# Robot-Power_V4_0.net
KiCad netlist of a schematic drawn in Altium Designer
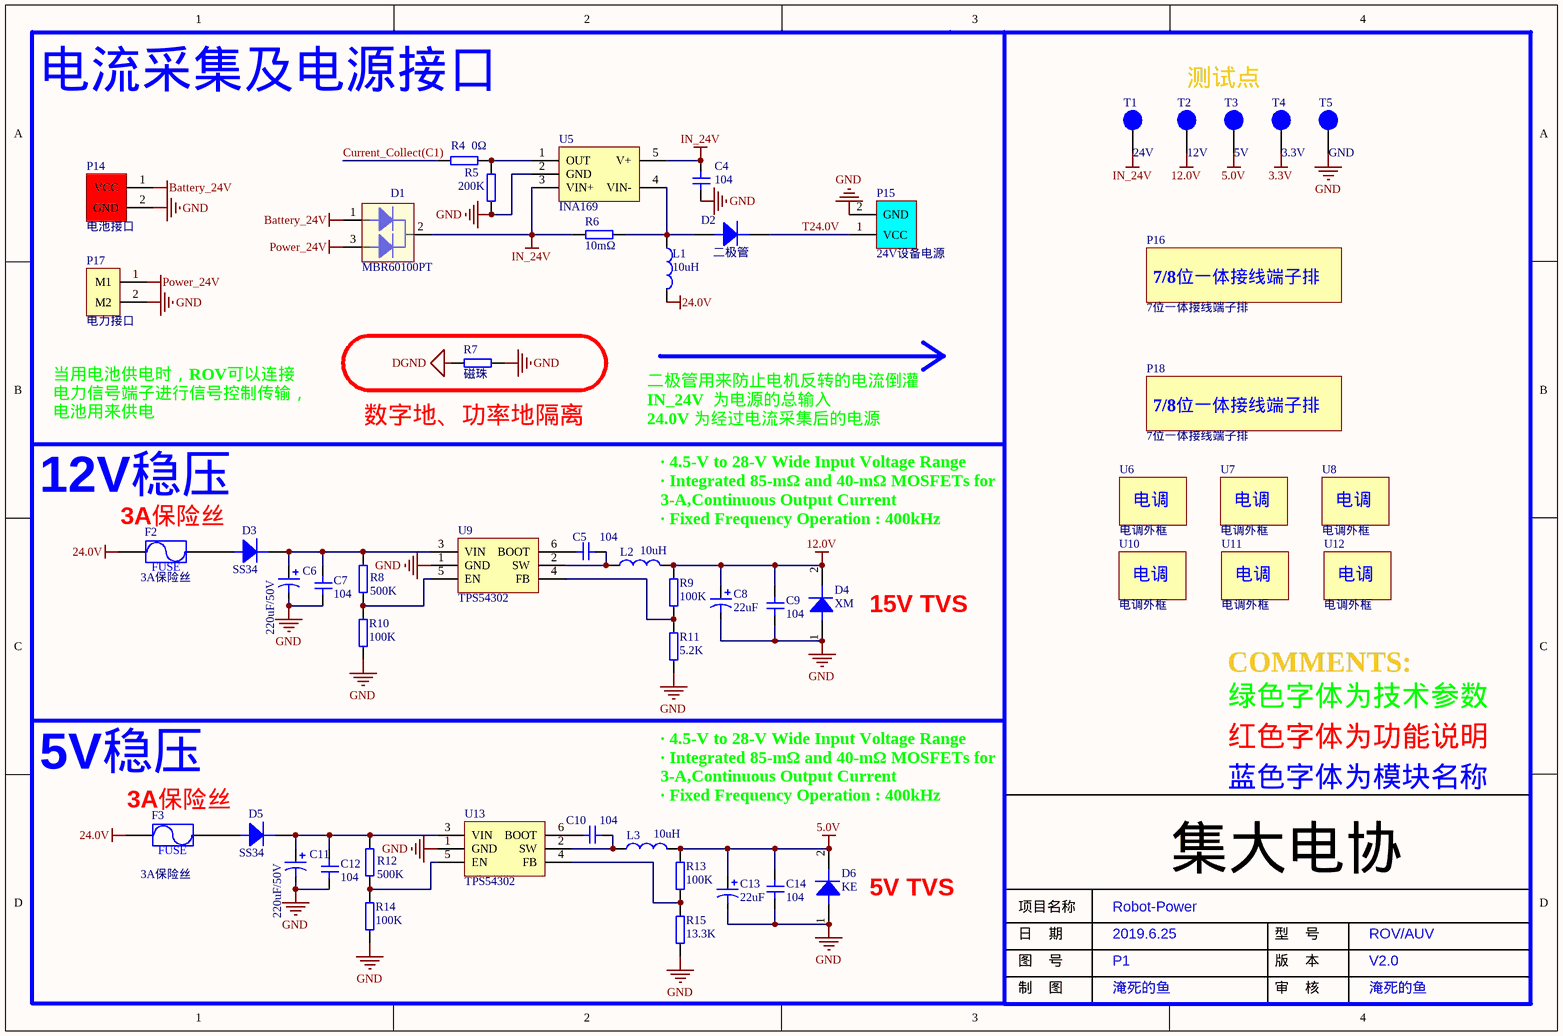
[diagram p0: Robot-Power V4.0.SchDoc]

(export (version "E")
  (design (tool "Eeschema 10.0.6"))
  (components
    (comp (ref "C4")
      (value "104")
      (footprint "0805C")
      (description "无极贴片电容")
      (libsource (lib "集大电协1.5") (part "Cap1"))
    )
    (comp (ref "C5")
      (value "104")
      (footprint "0805C")
      (description "无极贴片电容")
      (libsource (lib "集大电协1.5") (part "Cap1"))
    )
    (comp (ref "C6")
      (value "220uF/50V")
      (footprint "RB.1.2")
      (description "直插极性电容")
      (libsource (lib "集大电协1.5") (part "Cap3"))
    )
    (comp (ref "C7")
      (value "104")
      (footprint "0805C")
      (description "无极贴片电容")
      (libsource (lib "集大电协1.5") (part "Cap1"))
    )
    (comp (ref "C8")
      (value "22uF")
      (footprint "TAJ-C")
      (description "极性贴片电容")
      (libsource (lib "集大电协1.5") (part "Pol Cap"))
    )
    (comp (ref "C9")
      (value "104")
      (footprint "0805C")
      (description "无极贴片电容")
      (libsource (lib "集大电协1.5") (part "Cap1"))
    )
    (comp (ref "C10")
      (value "104")
      (footprint "0805C")
      (description "无极贴片电容")
      (libsource (lib "集大电协1.5") (part "Cap1"))
    )
    (comp (ref "C11")
      (value "220uF/50V")
      (footprint "RB.1.2")
      (description "直插极性电容")
      (libsource (lib "集大电协1.5") (part "Cap3"))
    )
    (comp (ref "C12")
      (value "104")
      (footprint "0805C")
      (description "无极贴片电容")
      (libsource (lib "集大电协1.5") (part "Cap1"))
    )
    (comp (ref "C13")
      (value "22uF")
      (footprint "TAJ-C")
      (description "极性贴片电容")
      (libsource (lib "集大电协1.5") (part "Pol Cap"))
    )
    (comp (ref "C14")
      (value "104")
      (footprint "0805C")
      (description "无极贴片电容")
      (libsource (lib "集大电协1.5") (part "Cap1"))
    )
    (comp (ref "D1")
      (value "MBR60100PT")
      (footprint "TO-247LS")
      (libsource (lib "集大电协1.5") (part "MBR60100PT"))
    )
    (comp (ref "D2") (value "二极管") (footprint "二极管(大功率)") (libsource (lib "集大电协2.0") (part "Diode")))
    (comp (ref "D3")
      (value "SS34")
      (footprint "SMA/DO-214AC")
      (description "二极管")
      (libsource (lib "") (part "Diode_1"))
    )
    (comp (ref "D4")
      (value "XM")
      (footprint "SMBJ")
      (description "二极管")
      (libsource (lib "集大电协1.5") (part "Diode"))
    )
    (comp (ref "D5")
      (value "SS34")
      (footprint "SMA/DO-214AC")
      (description "二极管")
      (libsource (lib "") (part "Diode_1"))
    )
    (comp (ref "D6")
      (value "KE")
      (footprint "SMBJ")
      (description "二极管")
      (libsource (lib "集大电协1.5") (part "Diode"))
    )
    (comp (ref "F2")
      (value "3A保险丝")
      (footprint "FUSE-1206")
      (description "保险丝")
      (libsource (lib "集大电协1.2") (part "Fuse"))
    )
    (comp (ref "F3")
      (value "3A保险丝")
      (footprint "FUSE-1206")
      (description "保险丝")
      (libsource (lib "集大电协1.2") (part "Fuse"))
    )
    (comp (ref "L1")
      (value "10uH")
      (footprint "CDRH124")
      (description "电感")
      (libsource (lib "集大电协1.5") (part "L"))
    )
    (comp (ref "L2")
      (value "10uH")
      (footprint "CDRH124")
      (description "电感")
      (libsource (lib "") (part "L_1"))
    )
    (comp (ref "L3")
      (value "10uH")
      (footprint "CDRH124")
      (description "电感")
      (libsource (lib "") (part "L_1"))
    )
    (comp (ref "P14") (value "电池接口") (footprint "XT60-F") (libsource (lib "集大电协1.5") (part "电源端子")))
    (comp (ref "P15") (value "24V设备电源") (footprint "XT60-F") (libsource (lib "集大电协1.5") (part "推进器电源")))
    (comp (ref "P16")
      (value "7位一体接线端子排")
      (footprint "7/8一体接线端子")
      (libsource (lib "集大电协1.5") (part "7位一体接线端子排"))
    )
    (comp (ref "P17")
      (value "电力接口")
      (footprint "XT60-F")
      (description "2PIN")
      (libsource (lib "集大电协1.5") (part "接线端子-2PIN"))
    )
    (comp (ref "P18")
      (value "7位一体接线端子排")
      (footprint "7/8一体接线端子")
      (libsource (lib "集大电协1.5") (part "7位一体接线端子排"))
    )
    (comp (ref "R4")
      (value "0Ω")
      (footprint "0805R")
      (description "电阻")
      (libsource (lib "集大电协1.5") (part "Res"))
    )
    (comp (ref "R5")
      (value "200K")
      (footprint "0805R")
      (description "电阻")
      (libsource (lib "集大电协1.5") (part "Res"))
    )
    (comp (ref "R6")
      (value "10mΩ")
      (footprint "2512R")
      (description "电阻")
      (libsource (lib "集大电协1.5") (part "Res"))
    )
    (comp (ref "R7")
      (value "磁珠")
      (footprint "1210R")
      (description "电阻")
      (libsource (lib "集大电协1.2") (part "Res"))
    )
    (comp (ref "R8")
      (value "500K")
      (footprint "0805R")
      (description "电阻")
      (libsource (lib "集大电协1.5") (part "Res"))
    )
    (comp (ref "R9")
      (value "100K")
      (footprint "0805R")
      (description "电阻")
      (libsource (lib "集大电协1.5") (part "Res"))
    )
    (comp (ref "R10")
      (value "100K")
      (footprint "0805R")
      (description "电阻")
      (libsource (lib "集大电协1.5") (part "Res"))
    )
    (comp (ref "R11")
      (value "5.2K")
      (footprint "0805R")
      (description "电阻")
      (libsource (lib "集大电协1.5") (part "Res"))
    )
    (comp (ref "R12")
      (value "500K")
      (footprint "0805R")
      (description "电阻")
      (libsource (lib "集大电协1.5") (part "Res"))
    )
    (comp (ref "R13")
      (value "100K")
      (footprint "0805R")
      (description "电阻")
      (libsource (lib "集大电协1.5") (part "Res"))
    )
    (comp (ref "R14")
      (value "100K")
      (footprint "0805R")
      (description "电阻")
      (libsource (lib "集大电协1.5") (part "Res"))
    )
    (comp (ref "R15")
      (value "13.3K")
      (footprint "0805R")
      (description "电阻")
      (libsource (lib "集大电协1.5") (part "Res"))
    )
    (comp (ref "T1")
      (value "24V")
      (footprint "HEADER 1")
      (description "测试点")
      (libsource (lib "集大电协1.2") (part "测试点"))
    )
    (comp (ref "T2")
      (value "12V")
      (footprint "HEADER 1")
      (description "测试点")
      (libsource (lib "集大电协1.2") (part "测试点"))
    )
    (comp (ref "T3")
      (value "5V")
      (footprint "HEADER 1")
      (description "测试点")
      (libsource (lib "集大电协1.2") (part "测试点"))
    )
    (comp (ref "T4")
      (value "3.3V")
      (footprint "HEADER 1")
      (description "测试点")
      (libsource (lib "集大电协1.2") (part "测试点"))
    )
    (comp (ref "T5")
      (value "GND")
      (footprint "HEADER 1")
      (description "测试点")
      (libsource (lib "集大电协1.2") (part "测试点"))
    )
    (comp (ref "U5") (value "INA169") (footprint "SOT23-5") (libsource (lib "集大电协1.5") (part "INA169")))
    (comp (ref "U6") (value "电调外框") (footprint "电调外框") (libsource (lib "集大电协1.5") (part "电调")))
    (comp (ref "U7") (value "电调外框") (footprint "电调外框") (libsource (lib "集大电协1.5") (part "电调")))
    (comp (ref "U8") (value "电调外框") (footprint "电调外框") (libsource (lib "集大电协1.5") (part "电调")))
    (comp (ref "U9") (value "TPS54302") (footprint "SOT23-6") (libsource (lib "集大电协1.5") (part "TPS54302")))
    (comp (ref "U10") (value "电调外框") (footprint "电调外框") (libsource (lib "集大电协1.5") (part "电调")))
    (comp (ref "U11") (value "电调外框") (footprint "电调外框") (libsource (lib "集大电协1.5") (part "电调")))
    (comp (ref "U12") (value "电调外框") (footprint "电调外框") (libsource (lib "集大电协1.5") (part "电调")))
    (comp (ref "U13") (value "TPS54302") (footprint "SOT23-6") (libsource (lib "集大电协1.5") (part "TPS54302")))
  )
  (nets
    (net (code "1") (name "/Current_Collect(C1)") (class "Default")
      (node (ref "R4") (pin "1") (pinfunction "1_1") (pintype "passive"))
    )
    (net (code "2") (name "/T24.0V") (class "Default")
      (node (ref "D2") (pin "2") (pinfunction "2_2") (pintype "passive"))
      (node (ref "P15") (pin "1") (pinfunction "VCC_1") (pintype "passive"))
    )
    (net (code "3") (name "3.3V") (class "Default")
      (node (ref "T4") (pin "1") (pinfunction "1_1") (pintype "passive"))
    )
    (net (code "4") (name "5.0V") (class "Default")
      (node (ref "C13") (pin "1") (pinfunction "1_1") (pintype "passive"))
      (node (ref "C14") (pin "2") (pinfunction "2_2") (pintype "passive"))
      (node (ref "D6") (pin "2") (pinfunction "2_2") (pintype "passive"))
      (node (ref "L3") (pin "2") (pinfunction "2_2") (pintype "passive"))
      (node (ref "R13") (pin "2") (pinfunction "2_2") (pintype "passive"))
      (node (ref "T3") (pin "1") (pinfunction "1_1") (pintype "passive"))
    )
    (net (code "5") (name "12.0V") (class "Default")
      (node (ref "C8") (pin "1") (pinfunction "1_1") (pintype "passive"))
      (node (ref "C9") (pin "2") (pinfunction "2_2") (pintype "passive"))
      (node (ref "D4") (pin "2") (pinfunction "2_2") (pintype "passive"))
      (node (ref "L2") (pin "2") (pinfunction "2_2") (pintype "passive"))
      (node (ref "R9") (pin "2") (pinfunction "2_2") (pintype "passive"))
      (node (ref "T2") (pin "1") (pinfunction "1_1") (pintype "passive"))
    )
    (net (code "6") (name "24.0V") (class "Default")
      (node (ref "F2") (pin "1") (pinfunction "1_1") (pintype "passive"))
      (node (ref "F3") (pin "1") (pinfunction "1_1") (pintype "passive"))
      (node (ref "L1") (pin "2") (pinfunction "2_2") (pintype "passive"))
    )
    (net (code "7") (name "Battery_24V") (class "Default")
      (node (ref "D1") (pin "1") (pintype "passive"))
      (node (ref "P14") (pin "1") (pinfunction "VCC_1") (pintype "passive"))
    )
    (net (code "8") (name "DGND") (class "Default")
      (node (ref "R7") (pin "2") (pinfunction "2_2") (pintype "passive"))
    )
    (net (code "9") (name "GND") (class "Default")
      (node (ref "C11") (pin "2") (pinfunction "2_2") (pintype "passive"))
      (node (ref "C12") (pin "1") (pinfunction "1_1") (pintype "passive"))
      (node (ref "C13") (pin "2") (pinfunction "2_2") (pintype "passive"))
      (node (ref "C14") (pin "1") (pinfunction "1_1") (pintype "passive"))
      (node (ref "C4") (pin "1") (pinfunction "1_1") (pintype "passive"))
      (node (ref "C6") (pin "2") (pinfunction "2_2") (pintype "passive"))
      (node (ref "C7") (pin "1") (pinfunction "1_1") (pintype "passive"))
      (node (ref "C8") (pin "2") (pinfunction "2_2") (pintype "passive"))
      (node (ref "C9") (pin "1") (pinfunction "1_1") (pintype "passive"))
      (node (ref "D4") (pin "1") (pintype "passive"))
      (node (ref "D6") (pin "1") (pintype "passive"))
      (node (ref "P14") (pin "2") (pinfunction "GND_2") (pintype "passive"))
      (node (ref "P15") (pin "2") (pinfunction "GND_2") (pintype "passive"))
      (node (ref "P17") (pin "2") (pinfunction "M2_2") (pintype "passive"))
      (node (ref "R10") (pin "1") (pinfunction "1_1") (pintype "passive"))
      (node (ref "R11") (pin "1") (pinfunction "1_1") (pintype "passive"))
      (node (ref "R14") (pin "1") (pinfunction "1_1") (pintype "passive"))
      (node (ref "R15") (pin "1") (pinfunction "1_1") (pintype "passive"))
      (node (ref "R5") (pin "2") (pinfunction "2_2") (pintype "passive"))
      (node (ref "R7") (pin "1") (pinfunction "1_1") (pintype "passive"))
      (node (ref "T5") (pin "1") (pinfunction "1_1") (pintype "passive"))
      (node (ref "U13") (pin "1") (pinfunction "GND_1") (pintype "passive"))
      (node (ref "U5") (pin "2") (pinfunction "GND_2") (pintype "passive"))
      (node (ref "U9") (pin "1") (pinfunction "GND_1") (pintype "passive"))
    )
    (net (code "10") (name "IN_24V") (class "Default")
      (node (ref "C4") (pin "2") (pinfunction "2_2") (pintype "passive"))
      (node (ref "D1") (pin "2") (pinfunction "2_2") (pintype "passive"))
      (node (ref "R6") (pin "2") (pinfunction "2_2") (pintype "passive"))
      (node (ref "T1") (pin "1") (pinfunction "1_1") (pintype "passive"))
      (node (ref "U5") (pin "3") (pinfunction "VIN+_3") (pintype "passive"))
      (node (ref "U5") (pin "5") (pinfunction "V+_5") (pintype "passive"))
    )
    (net (code "11") (name "Net-(D3-Pad1)") (class "Default")
      (node (ref "D3") (pin "1") (pintype "passive"))
      (node (ref "F2") (pin "2") (pinfunction "2_2") (pintype "passive"))
    )
    (net (code "12") (name "Net-(D5-Pad1)") (class "Default")
      (node (ref "D5") (pin "1") (pintype "passive"))
      (node (ref "F3") (pin "2") (pinfunction "2_2") (pintype "passive"))
    )
    (net (code "13") (name "Net-(U5-OUT)") (class "Default")
      (node (ref "R4") (pin "2") (pinfunction "2_2") (pintype "passive"))
      (node (ref "R5") (pin "1") (pinfunction "1_1") (pintype "passive"))
      (node (ref "U5") (pin "1") (pinfunction "OUT_1") (pintype "passive"))
    )
    (net (code "14") (name "Net-(U5-VIN-)") (class "Default")
      (node (ref "D2") (pin "1") (pinfunction "1_1") (pintype "passive"))
      (node (ref "L1") (pin "1") (pinfunction "1_1") (pintype "passive"))
      (node (ref "R6") (pin "1") (pinfunction "1_1") (pintype "passive"))
      (node (ref "U5") (pin "4") (pinfunction "VIN-_4") (pintype "passive"))
    )
    (net (code "15") (name "Net-(U9-BOOT)") (class "Default")
      (node (ref "C5") (pin "2") (pinfunction "2_2") (pintype "passive"))
      (node (ref "U9") (pin "6") (pinfunction "BOOT_6") (pintype "passive"))
    )
    (net (code "16") (name "Net-(U9-EN)") (class "Default")
      (node (ref "R10") (pin "2") (pinfunction "2_2") (pintype "passive"))
      (node (ref "R8") (pin "1") (pinfunction "1_1") (pintype "passive"))
      (node (ref "U9") (pin "5") (pinfunction "EN_5") (pintype "passive"))
    )
    (net (code "17") (name "Net-(U9-FB)") (class "Default")
      (node (ref "R11") (pin "2") (pinfunction "2_2") (pintype "passive"))
      (node (ref "R9") (pin "1") (pinfunction "1_1") (pintype "passive"))
      (node (ref "U9") (pin "4") (pinfunction "FB_4") (pintype "passive"))
    )
    (net (code "18") (name "Net-(U9-SW)") (class "Default")
      (node (ref "C5") (pin "1") (pinfunction "1_1") (pintype "passive"))
      (node (ref "L2") (pin "1") (pinfunction "1_1") (pintype "passive"))
      (node (ref "U9") (pin "2") (pinfunction "SW_2") (pintype "passive"))
    )
    (net (code "19") (name "Net-(U9-VIN)") (class "Default")
      (node (ref "C6") (pin "1") (pinfunction "1_1") (pintype "passive"))
      (node (ref "C7") (pin "2") (pinfunction "2_2") (pintype "passive"))
      (node (ref "D3") (pin "2") (pinfunction "2_2") (pintype "passive"))
      (node (ref "R8") (pin "2") (pinfunction "2_2") (pintype "passive"))
      (node (ref "U9") (pin "3") (pinfunction "VIN_3") (pintype "passive"))
    )
    (net (code "20") (name "Net-(U13-BOOT)") (class "Default")
      (node (ref "C10") (pin "2") (pinfunction "2_2") (pintype "passive"))
      (node (ref "U13") (pin "6") (pinfunction "BOOT_6") (pintype "passive"))
    )
    (net (code "21") (name "Net-(U13-EN)") (class "Default")
      (node (ref "R12") (pin "1") (pinfunction "1_1") (pintype "passive"))
      (node (ref "R14") (pin "2") (pinfunction "2_2") (pintype "passive"))
      (node (ref "U13") (pin "5") (pinfunction "EN_5") (pintype "passive"))
    )
    (net (code "22") (name "Net-(U13-FB)") (class "Default")
      (node (ref "R13") (pin "1") (pinfunction "1_1") (pintype "passive"))
      (node (ref "R15") (pin "2") (pinfunction "2_2") (pintype "passive"))
      (node (ref "U13") (pin "4") (pinfunction "FB_4") (pintype "passive"))
    )
    (net (code "23") (name "Net-(U13-SW)") (class "Default")
      (node (ref "C10") (pin "1") (pinfunction "1_1") (pintype "passive"))
      (node (ref "L3") (pin "1") (pinfunction "1_1") (pintype "passive"))
      (node (ref "U13") (pin "2") (pinfunction "SW_2") (pintype "passive"))
    )
    (net (code "24") (name "Net-(U13-VIN)") (class "Default")
      (node (ref "C11") (pin "1") (pinfunction "1_1") (pintype "passive"))
      (node (ref "C12") (pin "2") (pinfunction "2_2") (pintype "passive"))
      (node (ref "D5") (pin "2") (pinfunction "2_2") (pintype "passive"))
      (node (ref "R12") (pin "2") (pinfunction "2_2") (pintype "passive"))
      (node (ref "U13") (pin "3") (pinfunction "VIN_3") (pintype "passive"))
    )
    (net (code "25") (name "Power_24V") (class "Default")
      (node (ref "D1") (pin "3") (pintype "passive"))
      (node (ref "P17") (pin "1") (pinfunction "M1_1") (pintype "passive"))
    )
  )
)
